# 3V3_to_1V8.net
KiCad netlist of a schematic drawn in Altium Designer
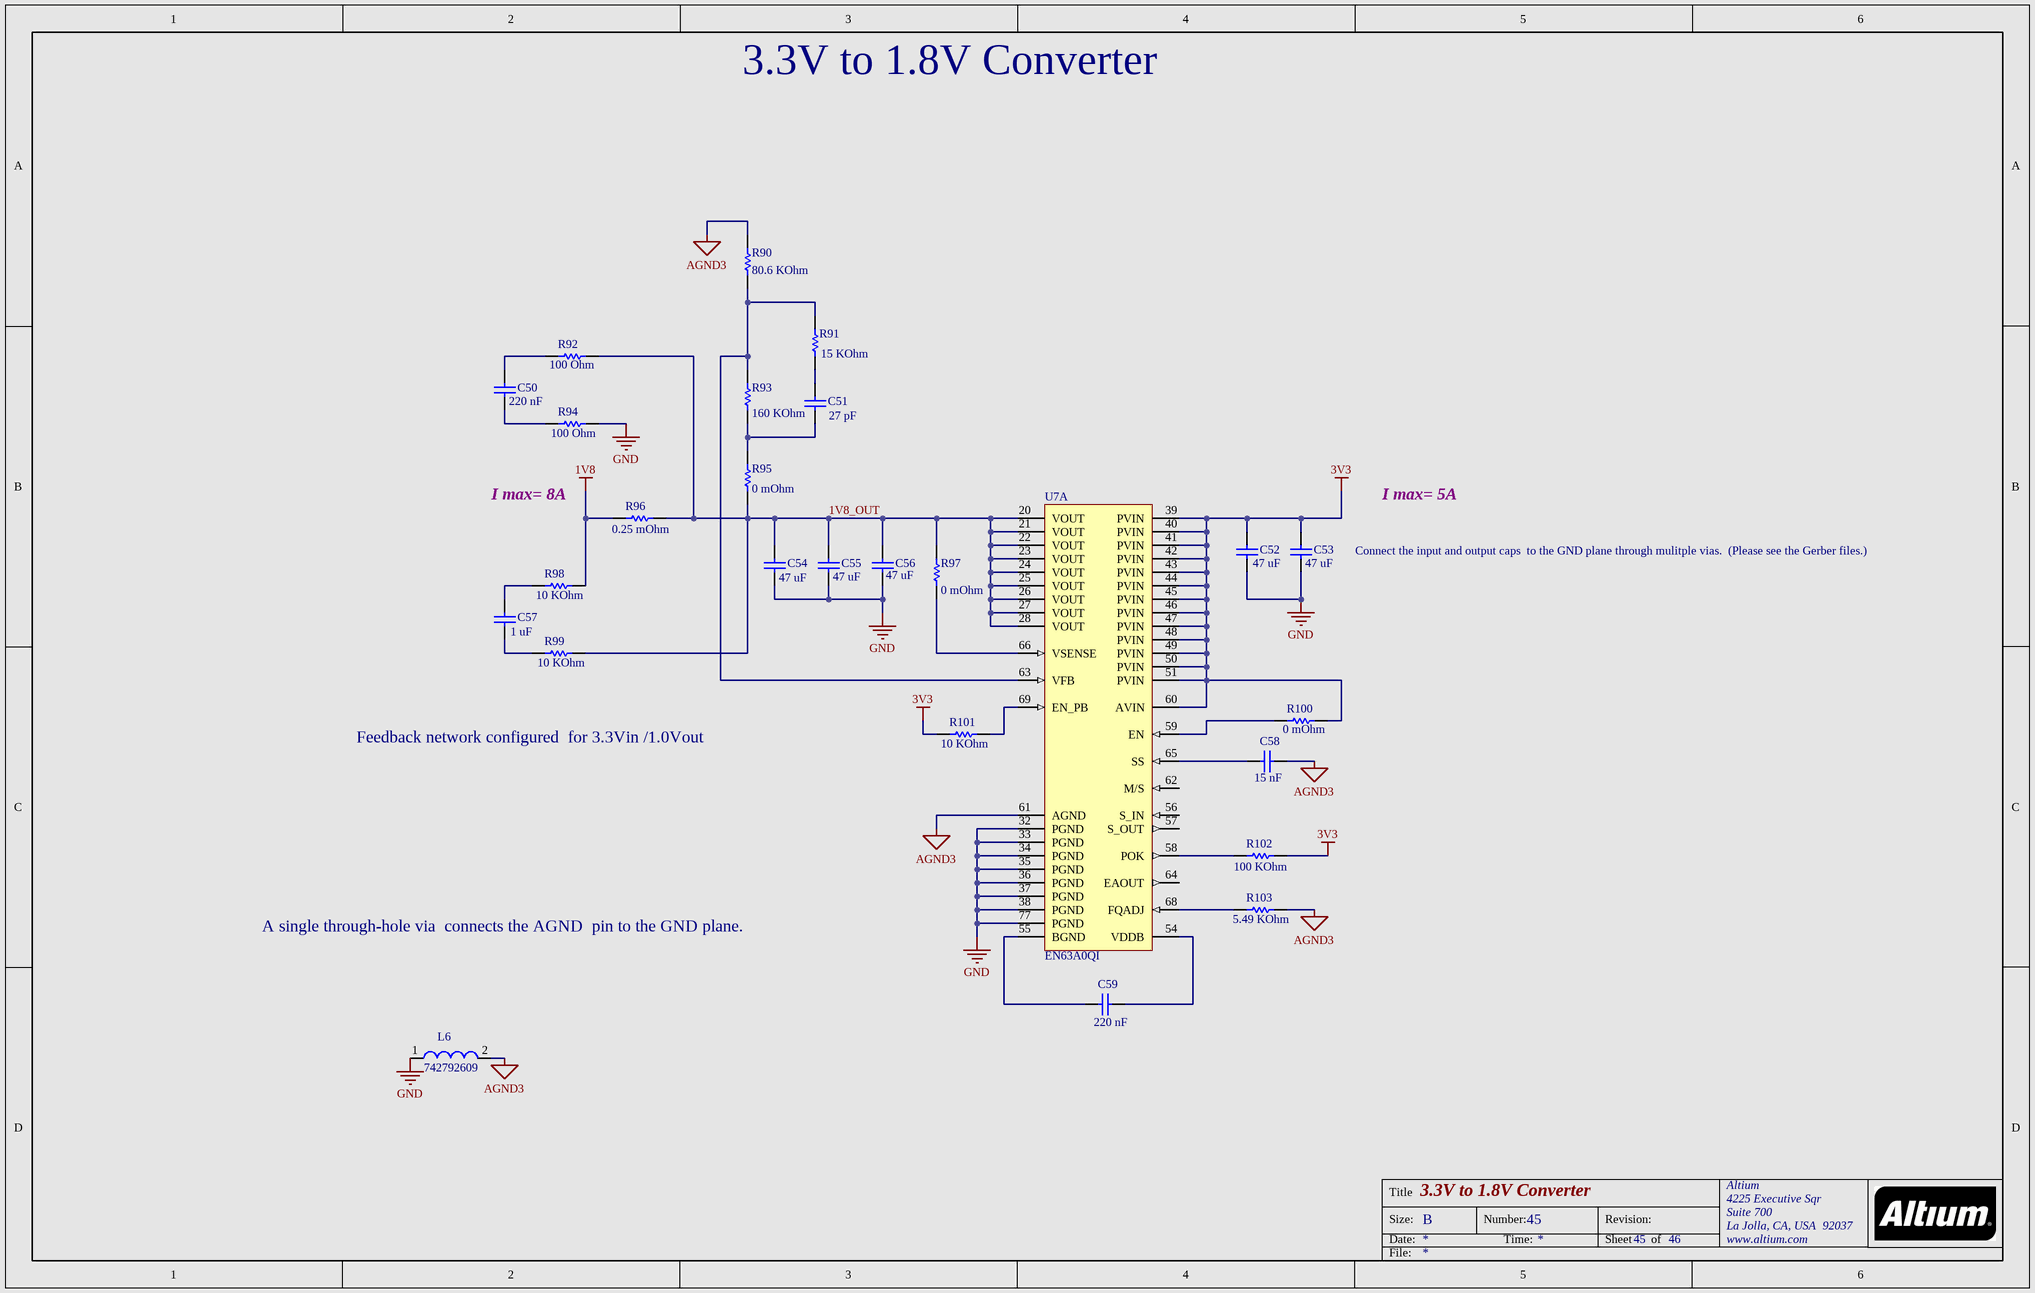
[diagram p0: 3V3_to_1V8.SchDoc]

(export (version "E")
  (design (tool "Eeschema 10.0.6"))
  (components
    (comp (ref "C50")
      (value "GRM155R61A224KE19D")
      (footprint "CAPC1005X55X25NL05T10")
      (description "Chip Capacitor, 220 nF, +/- 10%, 10 V, -55 to 85 degC, 0402 (1005 Metric), RoHS, Tape and Reel")
      (fields
        (field (name "TOLERANCE") "10%")
        (field (name "CAPACITANCE") "220 nF")
        (field (name "MANUFACTURER") "Basic Passives")
      )
      (libsource (lib "Altium Content Vault") (part "CAP-NP-2"))
    )
    (comp (ref "C51")
      (value "ECJ-0EC1H270J")
      (footprint "CAPC1005X55X20ML5T10")
      (description "Chip Capacitor, 27 pF, +/- 5%, 50 V, -55 to 125 degC, 0402 (1005 Metric), RoHS, Tape and Reel")
      (fields (field (name "TOLERANCE") "5%") (field (name "CAPACITANCE") "27 pF"))
      (libsource (lib "Altium Content Vault") (part "CMP-1665-00021-1"))
    )
    (comp (ref "C52")
      (value "C3216X5R1A476M160AB")
      (footprint "CAPC3216X180X20ML20")
      (description "Chip Capacitor, 47 uF, +/- 20%, 10 V, -55 to 85 degC, 1206 (3216 Metric), RoHS, Tape and Reel")
      (fields (field (name "TOLERANCE") "20%") (field (name "CAPACITANCE") "47 uF"))
      (libsource (lib "") (part "CAP-NP-2_1"))
    )
    (comp (ref "C53")
      (value "C3216X5R1A476M160AB")
      (footprint "CAPC3216X180X20ML20")
      (description "Chip Capacitor, 47 uF, +/- 20%, 10 V, -55 to 85 degC, 1206 (3216 Metric), RoHS, Tape and Reel")
      (fields (field (name "TOLERANCE") "20%") (field (name "CAPACITANCE") "47 uF"))
      (libsource (lib "") (part "CAP-NP-2_1"))
    )
    (comp (ref "C54")
      (value "C3216X5R1A476M160AB")
      (footprint "CAPC3216X180X20ML20")
      (description "Chip Capacitor, 47 uF, +/- 20%, 10 V, -55 to 85 degC, 1206 (3216 Metric), RoHS, Tape and Reel")
      (fields (field (name "TOLERANCE") "20%") (field (name "CAPACITANCE") "47 uF"))
      (libsource (lib "") (part "CAP-NP-2_1"))
    )
    (comp (ref "C55")
      (value "C3216X5R1A476M160AB")
      (footprint "CAPC3216X180X20ML20")
      (description "Chip Capacitor, 47 uF, +/- 20%, 10 V, -55 to 85 degC, 1206 (3216 Metric), RoHS, Tape and Reel")
      (fields (field (name "TOLERANCE") "20%") (field (name "CAPACITANCE") "47 uF"))
      (libsource (lib "") (part "CAP-NP-2_1"))
    )
    (comp (ref "C56")
      (value "C3216X5R1A476M160AB")
      (footprint "CAPC3216X180X20ML20")
      (description "Chip Capacitor, 47 uF, +/- 20%, 10 V, -55 to 85 degC, 1206 (3216 Metric), RoHS, Tape and Reel")
      (fields (field (name "TOLERANCE") "20%") (field (name "CAPACITANCE") "47 uF"))
      (libsource (lib "") (part "CAP-NP-2_1"))
    )
    (comp (ref "C57")
      (value "CGB2A1X5R1E105K033BC")
      (footprint "CAPC1005X33X10LL5")
      (description "Chip Capacitor, 1 uF, +/- 10%, 25 V, -55 to 85 degC, 0402 (1005 Metric), RoHS, Tape and Reel")
      (fields (field (name "TOLERANCE") "10%") (field (name "CAPACITANCE") "1 uF"))
      (libsource (lib "") (part "CAP-NP-2_1"))
    )
    (comp (ref "C58")
      (value "VJ0402Y153JXQPW1BC")
      (footprint "CAPC1005X55X23ML05T8")
      (description "Chip Capacitor, 15 nF, +/- 5%, 10 V, -55 to 125 degC, 0402 (1005 Metric), RoHS, Tape and Reel")
      (fields (field (name "CAPACITANCE") "15 nF") (field (name "TOLERANCE") "5%"))
      (libsource (lib "Altium Content Vault") (part "CAP-NP-2"))
    )
    (comp (ref "C59")
      (value "GRM155R61A224KE19D")
      (footprint "CAPC1005X55X25NL05T10")
      (description "Chip Capacitor, 220 nF, +/- 10%, 10 V, -55 to 85 degC, 0402 (1005 Metric), RoHS, Tape and Reel")
      (fields
        (field (name "TOLERANCE") "10%")
        (field (name "CAPACITANCE") "220 nF")
        (field (name "MANUFACTURER") "Basic Passives")
      )
      (libsource (lib "Altium Content Vault") (part "CAP-NP-2"))
    )
    (comp (ref "L6")
      (value "742792609")
      (footprint "SMD-0603")
      (description "SMD EMI Suppression Ferrite Bead WE-CBF, Z = 30 Ohm")
      (libsource (lib "Altium Content Vault") (part "CMP-0220-00193-1"))
    )
    (comp (ref "R90")
      (value "ERJ-2RKF8062X")
      (footprint "RESC1005X40X25ML05T05")
      (description "Chip Resistor, 80.6 KOhm, +/- 1%, 100 mW, -55 to 155 degC, 0402 (1005 Metric), RoHS, Tape and Reel")
      (fields
        (field (name "RESISTANCE") "80.6 KOhm")
        (field (name "TOLERANCE") "1%")
        (field (name "MANUFACTURER") "Basic Passives")
      )
      (libsource (lib "Altium Content Vault") (part "RES-2"))
    )
    (comp (ref "R91")
      (value "ERJ-2RKF1502X")
      (footprint "RESC1005X40X25ML05T05")
      (description "Chip Resistor, 15 KOhm, +/- 1%, 100 mW, -55 to 155 degC, 0402 (1005 Metric), RoHS, Tape and Reel")
      (fields
        (field (name "RESISTANCE") "15 KOhm")
        (field (name "TOLERANCE") "1%")
        (field (name "MANUFACTURER") "Basic Passives")
      )
      (libsource (lib "Altium Content Vault") (part "RES-2"))
    )
    (comp (ref "R92")
      (value "ERJ-2RKF1000X")
      (footprint "RESC1005X40X25LL05T05")
      (description "Chip Resistor, 100 Ohm, +/- 1%, 100 mW, -55 to 155 degC, 0402 (1005 Metric), RoHS, Tape and Reel")
      (fields
        (field (name "TOLERANCE") "1%")
        (field (name "RESISTANCE") "100 Ohm")
        (field (name "MANUFACTURER") "Basic Passives")
      )
      (libsource (lib "Altium Content Vault") (part "RES-2"))
    )
    (comp (ref "R93")
      (value "CRCW0402160KFKED")
      (footprint "RESC1005X40X25ML05T05")
      (description "Chip Resistor, 160 KOhm, +/- 1%, 63 mW, -55 to 155 degC, 0402 (1005 Metric), RoHS, Tape and Reel")
      (fields
        (field (name "TOLERANCE") "1%")
        (field (name "RESISTANCE") "160 KOhm")
        (field (name "MANUFACTURER") "Basic Passives")
      )
      (libsource (lib "Altium Content Vault") (part "RES-2"))
    )
    (comp (ref "R94")
      (value "ERJ-2RKF1000X")
      (footprint "RESC1005X40X25LL05T05")
      (description "Chip Resistor, 100 Ohm, +/- 1%, 100 mW, -55 to 155 degC, 0402 (1005 Metric), RoHS, Tape and Reel")
      (fields
        (field (name "TOLERANCE") "1%")
        (field (name "RESISTANCE") "100 Ohm")
        (field (name "MANUFACTURER") "Basic Passives")
      )
      (libsource (lib "Altium Content Vault") (part "RES-2"))
    )
    (comp (ref "R95")
      (value "ERJ-2GE0R00X")
      (footprint "RESC1005X40X25ML05T05")
      (description "Chip Resistor, 0 mOhm, +/- 5%, 100 mW, -55 to 155 degC, 0402 (1005 Metric), RoHS, Tape and Reel")
      (fields
        (field (name "TOLERANCE") "5%")
        (field (name "RESISTANCE") "0 mOhm")
        (field (name "MANUFACTURER") "Basic Passives")
      )
      (libsource (lib "Altium Content Vault") (part "RES-2"))
    )
    (comp (ref "R96")
      (value "CSS2725FTL250")
      (footprint "STAC-CSS2725-099H_V")
      (description "Chip Resistor, 0.25 mOhm, +/- 1%, 4 W, -55 to 225 degC, 2725 (6865 Metric), RoHS, Tape and Reel")
      (fields (field (name "TOLERANCE") "1%") (field (name "RESISTANCE") "0.25 mOhm"))
      (libsource (lib "Altium Content Vault") (part "RES-2"))
    )
    (comp (ref "R97")
      (value "ERJ-2GE0R00X")
      (footprint "RESC1005X40X25ML05T05")
      (description "Chip Resistor, 0 mOhm, +/- 5%, 100 mW, -55 to 155 degC, 0402 (1005 Metric), RoHS, Tape and Reel")
      (fields
        (field (name "TOLERANCE") "5%")
        (field (name "RESISTANCE") "0 mOhm")
        (field (name "MANUFACTURER") "Basic Passives")
      )
      (libsource (lib "Altium Content Vault") (part "RES-2"))
    )
    (comp (ref "R98")
      (value "ERJ-2RKF1002X")
      (footprint "RESC1005X40X25NL05T05")
      (description "Chip Resistor, 10 KOhm, +/- 1%, 100 mW, -55 to 155 degC, 0402 (1005 Metric), RoHS, Tape and Reel")
      (fields
        (field (name "TOLERANCE") "1%")
        (field (name "RESISTANCE") "10 KOhm")
        (field (name "MANUFACTURER") "Basic Passives")
      )
      (libsource (lib "Altium Content Vault") (part "RES-2"))
    )
    (comp (ref "R99")
      (value "ERJ-2RKF1002X")
      (footprint "RESC1005X40X25NL05T05")
      (description "Chip Resistor, 10 KOhm, +/- 1%, 100 mW, -55 to 155 degC, 0402 (1005 Metric), RoHS, Tape and Reel")
      (fields
        (field (name "TOLERANCE") "1%")
        (field (name "RESISTANCE") "10 KOhm")
        (field (name "MANUFACTURER") "Basic Passives")
      )
      (libsource (lib "Altium Content Vault") (part "RES-2"))
    )
    (comp (ref "R100")
      (value "ERJ-2GE0R00X")
      (footprint "RESC1005X40X25ML05T05")
      (description "Chip Resistor, 0 mOhm, +/- 5%, 100 mW, -55 to 155 degC, 0402 (1005 Metric), RoHS, Tape and Reel")
      (fields
        (field (name "TOLERANCE") "5%")
        (field (name "RESISTANCE") "0 mOhm")
        (field (name "MANUFACTURER") "Basic Passives")
      )
      (libsource (lib "Altium Content Vault") (part "RES-2"))
    )
    (comp (ref "R101")
      (value "ERJ-2RKF1002X")
      (footprint "RESC1005X40X25NL05T05")
      (description "Chip Resistor, 10 KOhm, +/- 1%, 100 mW, -55 to 155 degC, 0402 (1005 Metric), RoHS, Tape and Reel")
      (fields
        (field (name "TOLERANCE") "1%")
        (field (name "RESISTANCE") "10 KOhm")
        (field (name "MANUFACTURER") "Basic Passives")
      )
      (libsource (lib "Altium Content Vault") (part "RES-2"))
    )
    (comp (ref "R102")
      (value "ERJ-2RKF1003X")
      (footprint "RESC1005X40X25LL05T05")
      (description "Chip Resistor, 100 KOhm, +/- 1%, 100 mW, -55 to 155 degC, 0402 (1005 Metric), RoHS, Tape and Reel")
      (fields
        (field (name "RESISTANCE") "100 KOhm")
        (field (name "TOLERANCE") "1%")
        (field (name "MANUFACTURER") "Basic Passives")
      )
      (libsource (lib "Altium Content Vault") (part "RES-2"))
    )
    (comp (ref "R103")
      (value "ERJ-2RKF5491X")
      (footprint "RESC1005X40X25NL05T05")
      (description "Chip Resistor, 5.49 KOhm, +/- 1%, 100 mW, -55 to 155 degC, 0402 (1005 Metric), RoHS, Tape and Reel")
      (fields
        (field (name "TOLERANCE") "1%")
        (field (name "RESISTANCE") "5.49 KOhm")
        (field (name "MANUFACTURER") "Basic Passives")
      )
      (libsource (lib "Altium Content Vault") (part "RES-2"))
    )
    (comp (ref "U7")
      (value "EN63A0QI")
      (footprint "ALTR-QFN-76_A-305_V")
      (libsource (lib "Altium Content Vault") (part "ALTR-EN63A0QX-QFN76"))
    )
  )
  (nets
    (net (code "1") (name "/1V8_OUT") (class "Default")
      (node (ref "C54") (pin "2") (pinfunction "2_2") (pintype "passive"))
      (node (ref "C55") (pin "2") (pinfunction "2_2") (pintype "passive"))
      (node (ref "C56") (pin "2") (pinfunction "2_2") (pintype "passive"))
      (node (ref "R92") (pin "1") (pinfunction "1_1") (pintype "passive"))
      (node (ref "R95") (pin "1") (pinfunction "1_1") (pintype "passive"))
      (node (ref "R96") (pin "2") (pinfunction "2_2") (pintype "passive"))
      (node (ref "R97") (pin "2") (pinfunction "2_2") (pintype "passive"))
      (node (ref "R99") (pin "2") (pinfunction "2_2") (pintype "passive"))
      (node (ref "U7") (pin "20") (pinfunction "VOUT_20") (pintype "power_in"))
      (node (ref "U7") (pin "21") (pinfunction "VOUT_21") (pintype "power_in"))
      (node (ref "U7") (pin "22") (pinfunction "VOUT_22") (pintype "power_in"))
      (node (ref "U7") (pin "23") (pinfunction "VOUT_23") (pintype "power_in"))
      (node (ref "U7") (pin "24") (pinfunction "VOUT_24") (pintype "power_in"))
      (node (ref "U7") (pin "25") (pinfunction "VOUT_25") (pintype "power_in"))
      (node (ref "U7") (pin "26") (pinfunction "VOUT_26") (pintype "power_in"))
      (node (ref "U7") (pin "27") (pinfunction "VOUT_27") (pintype "power_in"))
      (node (ref "U7") (pin "28") (pinfunction "VOUT_28") (pintype "power_in"))
    )
    (net (code "2") (name "1V8") (class "Default")
      (node (ref "R96") (pin "1") (pinfunction "1_1") (pintype "passive"))
      (node (ref "R98") (pin "2") (pinfunction "2_2") (pintype "passive"))
    )
    (net (code "3") (name "3V3") (class "Default")
      (node (ref "C52") (pin "2") (pinfunction "2_2") (pintype "passive"))
      (node (ref "C53") (pin "2") (pinfunction "2_2") (pintype "passive"))
      (node (ref "R100") (pin "1") (pinfunction "1_1") (pintype "passive"))
      (node (ref "R101") (pin "1") (pinfunction "1_1") (pintype "passive"))
      (node (ref "R102") (pin "2") (pinfunction "2_2") (pintype "passive"))
      (node (ref "U7") (pin "39") (pinfunction "PVIN_39") (pintype "power_in"))
      (node (ref "U7") (pin "40") (pinfunction "PVIN_40") (pintype "power_in"))
      (node (ref "U7") (pin "41") (pinfunction "PVIN_41") (pintype "power_in"))
      (node (ref "U7") (pin "42") (pinfunction "PVIN_42") (pintype "power_in"))
      (node (ref "U7") (pin "43") (pinfunction "PVIN_43") (pintype "power_in"))
      (node (ref "U7") (pin "44") (pinfunction "PVIN_44") (pintype "power_in"))
      (node (ref "U7") (pin "45") (pinfunction "PVIN_45") (pintype "power_in"))
      (node (ref "U7") (pin "46") (pinfunction "PVIN_46") (pintype "power_in"))
      (node (ref "U7") (pin "47") (pinfunction "PVIN_47") (pintype "power_in"))
      (node (ref "U7") (pin "48") (pinfunction "PVIN_48") (pintype "power_in"))
      (node (ref "U7") (pin "49") (pinfunction "PVIN_49") (pintype "power_in"))
      (node (ref "U7") (pin "50") (pinfunction "PVIN_50") (pintype "power_in"))
      (node (ref "U7") (pin "51") (pinfunction "PVIN_51") (pintype "power_in"))
      (node (ref "U7") (pin "60") (pinfunction "AVIN_60") (pintype "power_in"))
    )
    (net (code "4") (name "AGND3") (class "Default")
      (node (ref "C58") (pin "1") (pinfunction "1_1") (pintype "passive"))
      (node (ref "L6") (pin "2") (pinfunction "2_2") (pintype "passive"))
      (node (ref "R103") (pin "2") (pinfunction "2_2") (pintype "passive"))
      (node (ref "R90") (pin "2") (pinfunction "2_2") (pintype "passive"))
      (node (ref "U7") (pin "61") (pinfunction "AGND_61") (pintype "power_in"))
    )
    (net (code "5") (name "GND") (class "Default")
      (node (ref "C52") (pin "1") (pinfunction "1_1") (pintype "passive"))
      (node (ref "C53") (pin "1") (pinfunction "1_1") (pintype "passive"))
      (node (ref "C54") (pin "1") (pinfunction "1_1") (pintype "passive"))
      (node (ref "C55") (pin "1") (pinfunction "1_1") (pintype "passive"))
      (node (ref "C56") (pin "1") (pinfunction "1_1") (pintype "passive"))
      (node (ref "L6") (pin "1") (pinfunction "1_1") (pintype "passive"))
      (node (ref "R94") (pin "1") (pinfunction "1_1") (pintype "passive"))
      (node (ref "U7") (pin "32") (pinfunction "PGND_32") (pintype "power_in"))
      (node (ref "U7") (pin "33") (pinfunction "PGND_33") (pintype "power_in"))
      (node (ref "U7") (pin "34") (pinfunction "PGND_34") (pintype "power_in"))
      (node (ref "U7") (pin "35") (pinfunction "PGND_35") (pintype "power_in"))
      (node (ref "U7") (pin "36") (pinfunction "PGND_36") (pintype "power_in"))
      (node (ref "U7") (pin "37") (pinfunction "PGND_37") (pintype "power_in"))
      (node (ref "U7") (pin "38") (pinfunction "PGND_38") (pintype "power_in"))
      (node (ref "U7") (pin "77") (pinfunction "PGND_77") (pintype "power_in"))
    )
    (net (code "6") (name "Net-(C50-Pad1)") (class "Default")
      (node (ref "C50") (pin "1") (pinfunction "1_1") (pintype "passive"))
      (node (ref "R92") (pin "2") (pinfunction "2_2") (pintype "passive"))
    )
    (net (code "7") (name "Net-(C50-Pad2)") (class "Default")
      (node (ref "C50") (pin "2") (pinfunction "2_2") (pintype "passive"))
      (node (ref "R94") (pin "2") (pinfunction "2_2") (pintype "passive"))
    )
    (net (code "8") (name "Net-(C51-Pad1)") (class "Default")
      (node (ref "C51") (pin "1") (pinfunction "1_1") (pintype "passive"))
      (node (ref "R93") (pin "1") (pinfunction "1_1") (pintype "passive"))
      (node (ref "R95") (pin "2") (pinfunction "2_2") (pintype "passive"))
    )
    (net (code "9") (name "Net-(C51-Pad2)") (class "Default")
      (node (ref "C51") (pin "2") (pinfunction "2_2") (pintype "passive"))
      (node (ref "R91") (pin "1") (pinfunction "1_1") (pintype "passive"))
    )
    (net (code "10") (name "Net-(C57-Pad1)") (class "Default")
      (node (ref "C57") (pin "1") (pinfunction "1_1") (pintype "passive"))
      (node (ref "R99") (pin "1") (pinfunction "1_1") (pintype "passive"))
    )
    (net (code "11") (name "Net-(C57-Pad2)") (class "Default")
      (node (ref "C57") (pin "2") (pinfunction "2_2") (pintype "passive"))
      (node (ref "R98") (pin "1") (pinfunction "1_1") (pintype "passive"))
    )
    (net (code "12") (name "Net-(U7A-BGND)") (class "Default")
      (node (ref "C59") (pin "1") (pinfunction "1_1") (pintype "passive"))
      (node (ref "U7") (pin "55") (pinfunction "BGND_55") (pintype "power_in"))
    )
    (net (code "13") (name "Net-(U7A-EN)") (class "Default")
      (node (ref "R100") (pin "2") (pinfunction "2_2") (pintype "passive"))
      (node (ref "U7") (pin "59") (pinfunction "EN_59") (pintype "input"))
    )
    (net (code "14") (name "Net-(U7A-EN_PB)") (class "Default")
      (node (ref "R101") (pin "2") (pinfunction "2_2") (pintype "passive"))
      (node (ref "U7") (pin "69") (pinfunction "EN_PB_69") (pintype "input"))
    )
    (net (code "15") (name "Net-(U7A-FQADJ)") (class "Default")
      (node (ref "R103") (pin "1") (pinfunction "1_1") (pintype "passive"))
      (node (ref "U7") (pin "68") (pinfunction "FQADJ_68") (pintype "input"))
    )
    (net (code "16") (name "Net-(U7A-POK)") (class "Default")
      (node (ref "R102") (pin "1") (pinfunction "1_1") (pintype "passive"))
      (node (ref "U7") (pin "58") (pinfunction "POK_58") (pintype "output"))
    )
    (net (code "17") (name "Net-(U7A-SS)") (class "Default")
      (node (ref "C58") (pin "2") (pinfunction "2_2") (pintype "passive"))
      (node (ref "U7") (pin "65") (pinfunction "SS_65") (pintype "input"))
    )
    (net (code "18") (name "Net-(U7A-VDDB)") (class "Default")
      (node (ref "C59") (pin "2") (pinfunction "2_2") (pintype "passive"))
      (node (ref "U7") (pin "54") (pinfunction "VDDB_54") (pintype "power_in"))
    )
    (net (code "19") (name "Net-(U7A-VFB)") (class "Default")
      (node (ref "R90") (pin "1") (pinfunction "1_1") (pintype "passive"))
      (node (ref "R91") (pin "2") (pinfunction "2_2") (pintype "passive"))
      (node (ref "R93") (pin "2") (pinfunction "2_2") (pintype "passive"))
      (node (ref "U7") (pin "63") (pinfunction "VFB_63") (pintype "input"))
    )
    (net (code "20") (name "Net-(U7A-VSENSE)") (class "Default")
      (node (ref "R97") (pin "1") (pinfunction "1_1") (pintype "passive"))
      (node (ref "U7") (pin "66") (pinfunction "VSENSE_66") (pintype "input"))
    )
    (net (code "21") (name "unconnected-(U7A-EAOUT-Pad64)") (class "Default")
      (node (ref "U7") (pin "64") (pinfunction "EAOUT_64") (pintype "output"))
    )
    (net (code "22") (name "unconnected-(U7A-M{slash}S-Pad62)") (class "Default")
      (node (ref "U7") (pin "62") (pinfunction "M/S_62") (pintype "input"))
    )
    (net (code "23") (name "unconnected-(U7A-S_IN-Pad56)") (class "Default")
      (node (ref "U7") (pin "56") (pinfunction "S_IN_56") (pintype "input"))
    )
    (net (code "24") (name "unconnected-(U7A-S_OUT-Pad57)") (class "Default")
      (node (ref "U7") (pin "57") (pinfunction "S_OUT_57") (pintype "output"))
    )
  )
)
